# main.net
KiCad netlist of a schematic drawn in EAGLE
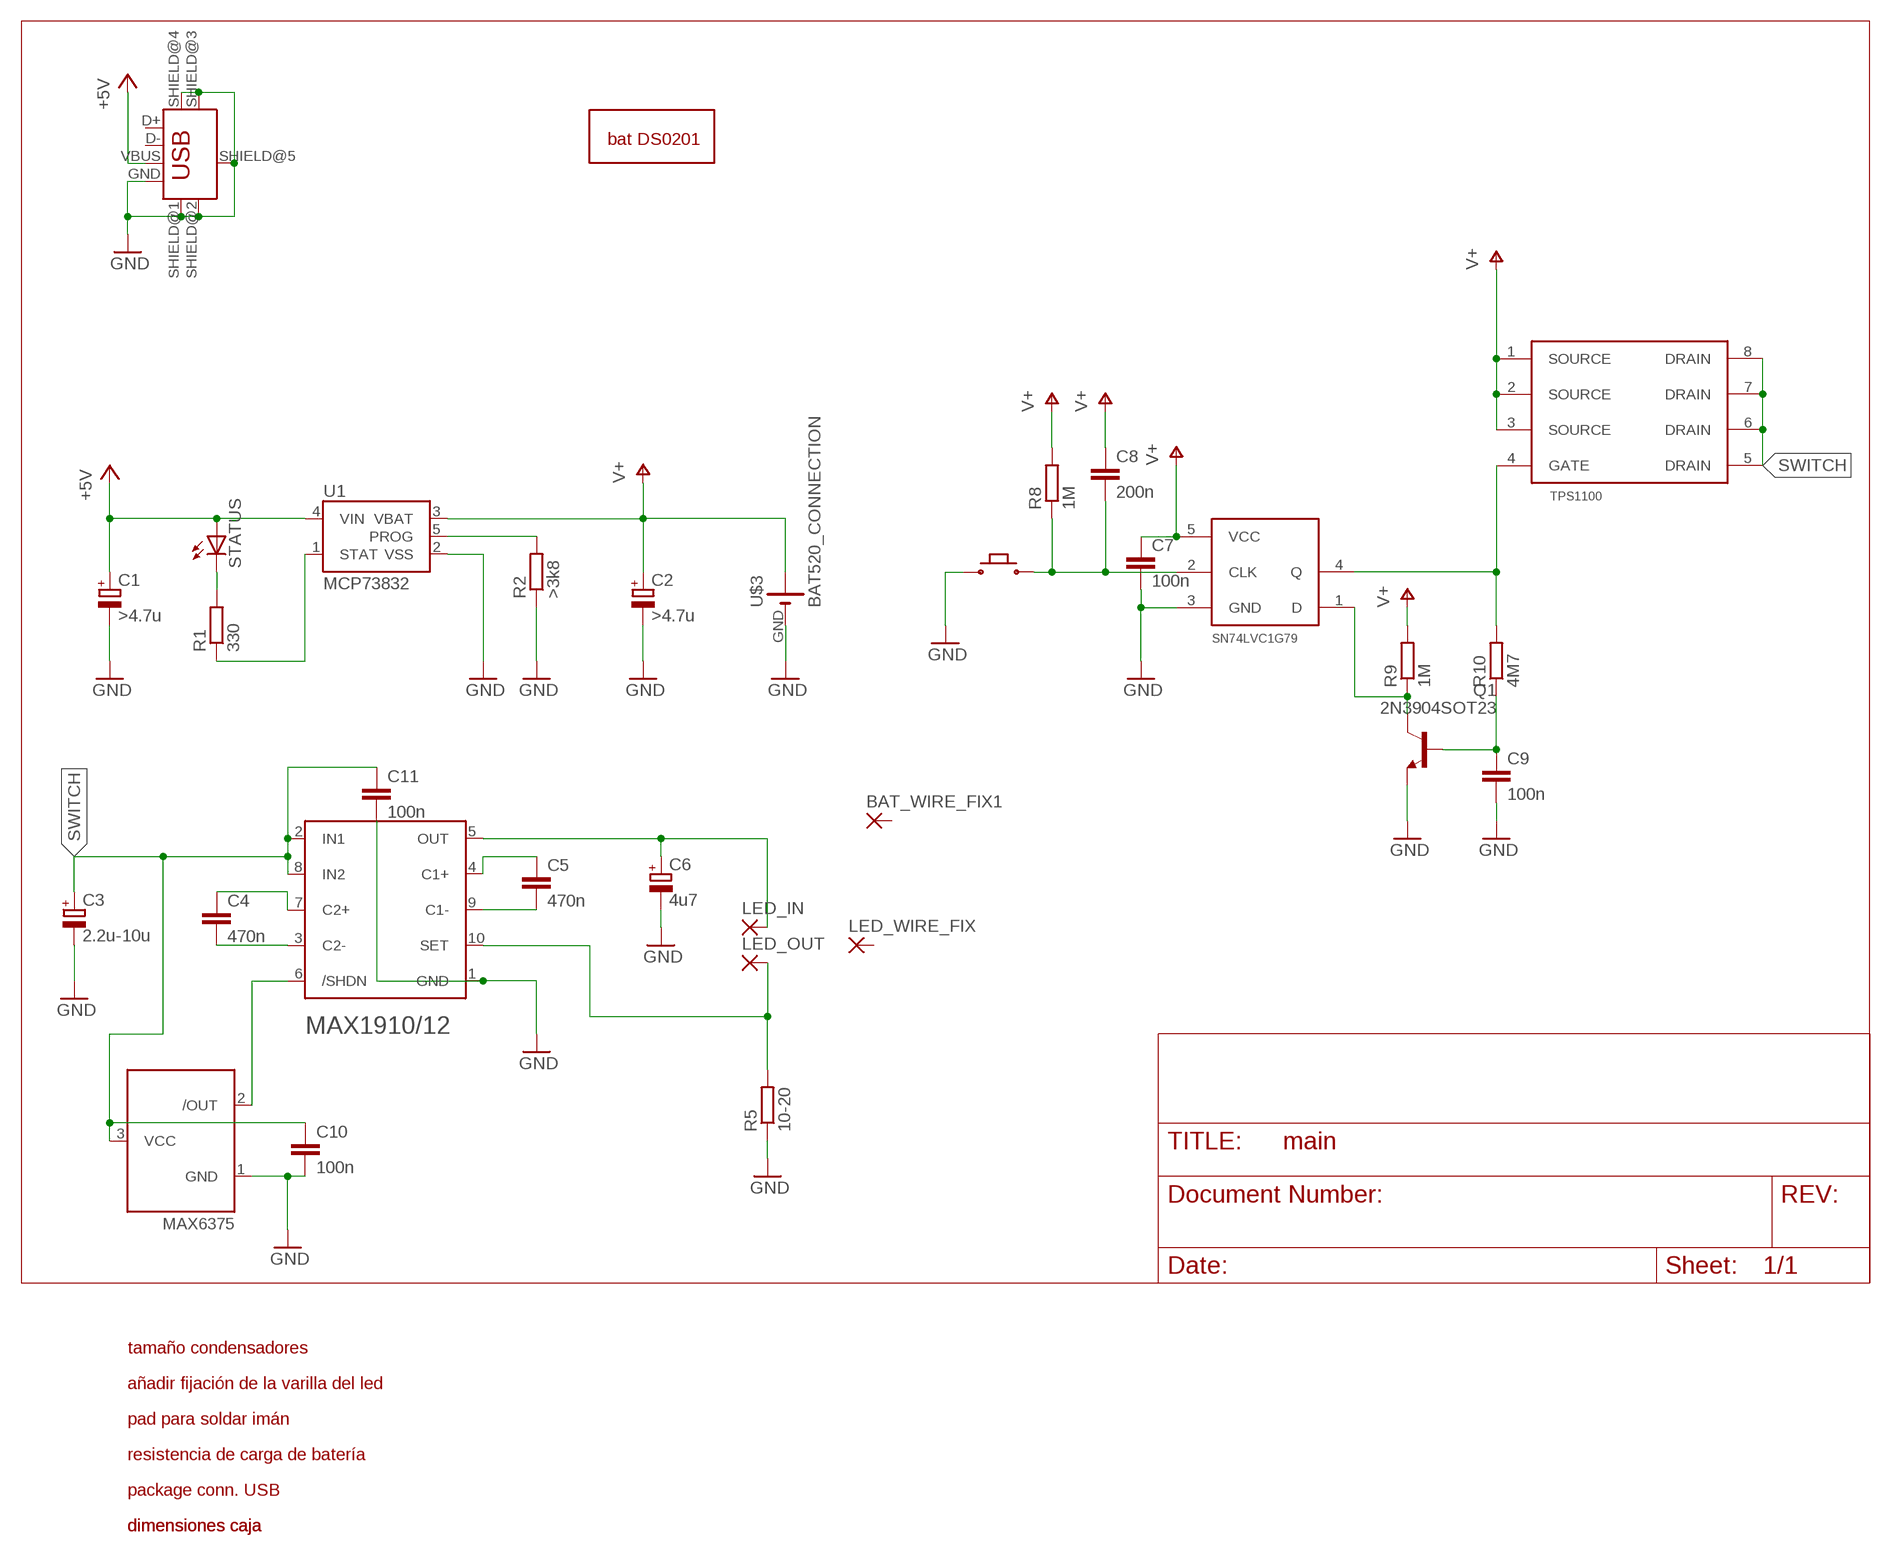
[diagram p0: schematic, sheet 1]

(export (version "E")
  (design (tool "Eeschema 10.0.6"))
  (components
    (comp (ref "BAT_WIRE_FIX1")
      (value "SMD5")
      (footprint "eagle-import:SMD2,54-5,08")
      (libsource (lib "eagle-import") (part "SMD5"))
    )
    (comp (ref "C1")
      (value ">4.7u")
      (footprint "eagle-import:SMC_B")
      (libsource (lib "eagle-import") (part "CPOL-EUSMCB"))
    )
    (comp (ref "C2")
      (value ">4.7u")
      (footprint "eagle-import:SMC_B")
      (libsource (lib "eagle-import") (part "CPOL-EUSMCB"))
    )
    (comp (ref "C3")
      (value "2.2u-10u")
      (footprint "eagle-import:SMC_B")
      (libsource (lib "eagle-import") (part "CPOL-EUSMCB"))
    )
    (comp (ref "C4")
      (value "470n")
      (footprint "eagle-import:C1206")
      (libsource (lib "eagle-import") (part "C-EUC1206"))
    )
    (comp (ref "C5")
      (value "470n")
      (footprint "eagle-import:C1206")
      (libsource (lib "eagle-import") (part "C-EUC1206"))
    )
    (comp (ref "C6")
      (value "4u7")
      (footprint "eagle-import:SMC_B")
      (libsource (lib "eagle-import") (part "CPOL-EUSMCB"))
    )
    (comp (ref "C7")
      (value "100n")
      (footprint "eagle-import:C1206")
      (libsource (lib "eagle-import") (part "C-EUC1206"))
    )
    (comp (ref "C8")
      (value "200n")
      (footprint "eagle-import:C1206")
      (libsource (lib "eagle-import") (part "C-EUC1206"))
    )
    (comp (ref "C9")
      (value "100n")
      (footprint "eagle-import:C1206")
      (libsource (lib "eagle-import") (part "C-EUC1206"))
    )
    (comp (ref "C10")
      (value "100n")
      (footprint "eagle-import:C1206")
      (libsource (lib "eagle-import") (part "C-EUC1206"))
    )
    (comp (ref "C11")
      (value "100n")
      (footprint "eagle-import:C1206")
      (libsource (lib "eagle-import") (part "C-EUC1206"))
    )
    (comp (ref "LED_IN")
      (value "SMD2")
      (footprint "eagle-import:SMD1,27-2,54")
      (libsource (lib "eagle-import") (part "SMD2"))
    )
    (comp (ref "LED_OUT")
      (value "SMD2")
      (footprint "eagle-import:SMD1,27-2,54")
      (libsource (lib "eagle-import") (part "SMD2"))
    )
    (comp (ref "LED_WIRE_FIX")
      (value "SMD5")
      (footprint "eagle-import:SMD2,54-5,08")
      (libsource (lib "eagle-import") (part "SMD5"))
    )
    (comp (ref "Q1")
      (value "2N3904SOT23")
      (footprint "eagle-import:SOT23")
      (libsource (lib "eagle-import") (part "2N3904SOT23"))
    )
    (comp (ref "R1")
      (value "330")
      (footprint "eagle-import:R1206")
      (libsource (lib "eagle-import") (part "R-EU_R1206"))
    )
    (comp (ref "R2")
      (value ">3k8")
      (footprint "eagle-import:R1206")
      (libsource (lib "eagle-import") (part "R-EU_R1206"))
    )
    (comp (ref "R5")
      (value "10-20")
      (footprint "eagle-import:R1206")
      (libsource (lib "eagle-import") (part "R-EU_R1206"))
    )
    (comp (ref "R8")
      (value "1M")
      (footprint "eagle-import:R0805")
      (libsource (lib "eagle-import") (part "R-EU_R0805"))
    )
    (comp (ref "R9")
      (value "1M")
      (footprint "eagle-import:R0805")
      (libsource (lib "eagle-import") (part "R-EU_R0805"))
    )
    (comp (ref "R10")
      (value "4M7")
      (footprint "eagle-import:R1206")
      (libsource (lib "eagle-import") (part "R-EU_R1206"))
    )
    (comp (ref "STATUS")
      (value "LEDCHIPLED_1206")
      (footprint "eagle-import:CHIPLED_1206")
      (libsource (lib "eagle-import") (part "LEDCHIPLED_1206"))
    )
    (comp (ref "U$1")
      (value "MAX1910/12")
      (footprint "eagle-import:UMAX_USOP_10L")
      (libsource (lib "eagle-import") (part "MAX1910/12"))
    )
    (comp (ref "U$2")
      (value "MAX6375")
      (footprint "eagle-import:SC70-3-W")
      (libsource (lib "eagle-import") (part "MAX6375"))
    )
    (comp (ref "U$3")
      (value "BAT520_CONNECTION")
      (footprint "eagle-import:BAT520_CONN_SMD")
      (libsource (lib "eagle-import") (part "BAT520_CONNECTION"))
    )
    (comp (ref "U$4")
      (value "BAT_DS0201_PACKAGE")
      (footprint "eagle-import:BAT_DS0201")
      (libsource (lib "eagle-import") (part "BAT_DS0201_PACKAGE"))
    )
    (comp (ref "U$5")
      (value "MICROUSB_B")
      (footprint "eagle-import:USB-MICROB")
      (libsource (lib "eagle-import") (part "MICROUSB_B"))
    )
    (comp (ref "U$6")
      (value "MICROBUTTONE-MERCHAN")
      (footprint "eagle-import:MICROBUTTON_2")
      (libsource (lib "eagle-import") (part "MICROBUTTONE-MERCHAN"))
    )
    (comp (ref "U$7")
      (value "SN74LVC1G79")
      (footprint "eagle-import:SOT23-5")
      (libsource (lib "eagle-import") (part "SN74LVC1G79"))
    )
    (comp (ref "U$8")
      (value "TPS1100")
      (footprint "eagle-import:SO08")
      (libsource (lib "eagle-import") (part "TPS1100"))
    )
    (comp (ref "U1")
      (value "MCP73832")
      (footprint "eagle-import:SOT23-5")
      (libsource (lib "eagle-import") (part "MCP73832"))
    )
  )
  (nets
    (net (code "1") (name "+5V") (class "Default")
      (node (ref "C1") (pin "+") (pinfunction "+_+") (pintype "passive"))
      (node (ref "STATUS") (pin "A") (pinfunction "A_A") (pintype "passive"))
      (node (ref "U$5") (pin "VBUS") (pinfunction "VBUS_VBUS") (pintype "bidirectional"))
      (node (ref "U1") (pin "4") (pinfunction "VIN_4") (pintype "power_in"))
    )
    (net (code "2") (name "GND") (class "Default")
      (node (ref "C1") (pin "-") (pinfunction "-_-") (pintype "passive"))
      (node (ref "C10") (pin "2") (pinfunction "2_2") (pintype "passive"))
      (node (ref "C11") (pin "2") (pinfunction "2_2") (pintype "passive"))
      (node (ref "C2") (pin "-") (pinfunction "-_-") (pintype "passive"))
      (node (ref "C3") (pin "-") (pinfunction "-_-") (pintype "passive"))
      (node (ref "C6") (pin "-") (pinfunction "-_-") (pintype "passive"))
      (node (ref "C7") (pin "2") (pinfunction "2_2") (pintype "passive"))
      (node (ref "C9") (pin "2") (pinfunction "2_2") (pintype "passive"))
      (node (ref "Q1") (pin "2") (pinfunction "E_2") (pintype "passive"))
      (node (ref "R2") (pin "1") (pinfunction "1_1") (pintype "passive"))
      (node (ref "R5") (pin "1") (pinfunction "1_1") (pintype "passive"))
      (node (ref "U$1") (pin "1") (pinfunction "GND_1") (pintype "power_in"))
      (node (ref "U$2") (pin "1") (pinfunction "GND_1") (pintype "power_in"))
      (node (ref "U$3") (pin "GND") (pinfunction "-_GND") (pintype "passive"))
      (node (ref "U$5") (pin "GND") (pinfunction "GND_GND") (pintype "bidirectional"))
      (node (ref "U$5") (pin "SHIELD@1") (pinfunction "SHIELD_SHIELD@1") (pintype "bidirectional"))
      (node (ref "U$5") (pin "SHIELD@2") (pinfunction "SHIELD_SHIELD@2") (pintype "bidirectional"))
      (node (ref "U$5") (pin "SHIELD@3") (pinfunction "SHIELD_SHIELD@3") (pintype "bidirectional"))
      (node (ref "U$5") (pin "SHIELD@4") (pinfunction "SHIELD_SHIELD@4") (pintype "bidirectional"))
      (node (ref "U$5") (pin "SHIELD@5") (pinfunction "SHIELD_SHIELD@5") (pintype "bidirectional"))
      (node (ref "U$6") (pin "P$1") (pinfunction "P$1_P$1") (pintype "bidirectional"))
      (node (ref "U$7") (pin "3") (pinfunction "GND_3") (pintype "bidirectional"))
      (node (ref "U1") (pin "2") (pinfunction "VSS_2") (pintype "power_in"))
    )
    (net (code "3") (name "Net-(LED_IN-P)") (class "Default")
      (node (ref "C6") (pin "+") (pinfunction "+_+") (pintype "passive"))
      (node (ref "LED_IN") (pin "1") (pinfunction "P_1") (pintype "passive"))
      (node (ref "U$1") (pin "5") (pinfunction "OUT_5") (pintype "output"))
    )
    (net (code "4") (name "Net-(LED_OUT-P)") (class "Default")
      (node (ref "LED_OUT") (pin "1") (pinfunction "P_1") (pintype "passive"))
      (node (ref "R5") (pin "2") (pinfunction "2_2") (pintype "passive"))
      (node (ref "U$1") (pin "10") (pinfunction "SET_10") (pintype "input"))
    )
    (net (code "5") (name "Net-(Q1-B)") (class "Default")
      (node (ref "C9") (pin "1") (pinfunction "1_1") (pintype "passive"))
      (node (ref "Q1") (pin "1") (pinfunction "B_1") (pintype "passive"))
      (node (ref "R10") (pin "1") (pinfunction "1_1") (pintype "passive"))
    )
    (net (code "6") (name "Net-(Q1-C)") (class "Default")
      (node (ref "Q1") (pin "3") (pinfunction "C_3") (pintype "passive"))
      (node (ref "R9") (pin "1") (pinfunction "1_1") (pintype "passive"))
      (node (ref "U$7") (pin "1") (pinfunction "D_1") (pintype "bidirectional"))
    )
    (net (code "7") (name "Net-(R1-Pad2)") (class "Default")
      (node (ref "R1") (pin "2") (pinfunction "2_2") (pintype "passive"))
      (node (ref "STATUS") (pin "C") (pinfunction "C_C") (pintype "passive"))
    )
    (net (code "8") (name "Net-(U$1-C1+)") (class "Default")
      (node (ref "C5") (pin "1") (pinfunction "1_1") (pintype "passive"))
      (node (ref "U$1") (pin "4") (pinfunction "C1+_4") (pintype "bidirectional"))
    )
    (net (code "9") (name "Net-(U$1-C1-)") (class "Default")
      (node (ref "C5") (pin "2") (pinfunction "2_2") (pintype "passive"))
      (node (ref "U$1") (pin "9") (pinfunction "C1-_9") (pintype "bidirectional"))
    )
    (net (code "10") (name "Net-(U$1-C2+)") (class "Default")
      (node (ref "C4") (pin "1") (pinfunction "1_1") (pintype "passive"))
      (node (ref "U$1") (pin "7") (pinfunction "C2+_7") (pintype "bidirectional"))
    )
    (net (code "11") (name "Net-(U$1-C2-)") (class "Default")
      (node (ref "C4") (pin "2") (pinfunction "2_2") (pintype "passive"))
      (node (ref "U$1") (pin "3") (pinfunction "C2-_3") (pintype "bidirectional"))
    )
    (net (code "12") (name "Net-(U$1-{slash}SHDN)") (class "Default")
      (node (ref "U$1") (pin "6") (pinfunction "/SHDN_6") (pintype "bidirectional"))
      (node (ref "U$2") (pin "2") (pinfunction "/OUT_2") (pintype "output"))
    )
    (net (code "13") (name "Net-(U$7-CLK)") (class "Default")
      (node (ref "C8") (pin "2") (pinfunction "2_2") (pintype "passive"))
      (node (ref "R8") (pin "1") (pinfunction "1_1") (pintype "passive"))
      (node (ref "U$6") (pin "P$2") (pinfunction "P$2_P$2") (pintype "bidirectional"))
      (node (ref "U$7") (pin "2") (pinfunction "CLK_2") (pintype "bidirectional"))
    )
    (net (code "14") (name "Net-(U$7-Q)") (class "Default")
      (node (ref "R10") (pin "2") (pinfunction "2_2") (pintype "passive"))
      (node (ref "U$7") (pin "4") (pinfunction "Q_4") (pintype "bidirectional"))
      (node (ref "U$8") (pin "4") (pinfunction "GATE_4") (pintype "bidirectional"))
    )
    (net (code "15") (name "Net-(U1-PROG)") (class "Default")
      (node (ref "R2") (pin "2") (pinfunction "2_2") (pintype "passive"))
      (node (ref "U1") (pin "5") (pinfunction "PROG_5") (pintype "input"))
    )
    (net (code "16") (name "Net-(U1-STAT)") (class "Default")
      (node (ref "R1") (pin "1") (pinfunction "1_1") (pintype "passive"))
      (node (ref "U1") (pin "1") (pinfunction "STAT_1") (pintype "output"))
    )
    (net (code "17") (name "SWITCH") (class "Default")
      (node (ref "C10") (pin "1") (pinfunction "1_1") (pintype "passive"))
      (node (ref "C11") (pin "1") (pinfunction "1_1") (pintype "passive"))
      (node (ref "C3") (pin "+") (pinfunction "+_+") (pintype "passive"))
      (node (ref "U$1") (pin "2") (pinfunction "IN1_2") (pintype "power_in"))
      (node (ref "U$1") (pin "8") (pinfunction "IN2_8") (pintype "power_in"))
      (node (ref "U$2") (pin "3") (pinfunction "VCC_3") (pintype "power_in"))
      (node (ref "U$8") (pin "5") (pinfunction "DRAIN_5") (pintype "bidirectional"))
      (node (ref "U$8") (pin "6") (pinfunction "DRAIN_6") (pintype "bidirectional"))
      (node (ref "U$8") (pin "7") (pinfunction "DRAIN_7") (pintype "bidirectional"))
      (node (ref "U$8") (pin "8") (pinfunction "DRAIN_8") (pintype "bidirectional"))
    )
    (net (code "18") (name "V+") (class "Default")
      (node (ref "C2") (pin "+") (pinfunction "+_+") (pintype "passive"))
      (node (ref "C7") (pin "1") (pinfunction "1_1") (pintype "passive"))
      (node (ref "C8") (pin "1") (pinfunction "1_1") (pintype "passive"))
      (node (ref "R8") (pin "2") (pinfunction "2_2") (pintype "passive"))
      (node (ref "R9") (pin "2") (pinfunction "2_2") (pintype "passive"))
      (node (ref "U$3") (pin "VCC") (pinfunction "+_VCC") (pintype "passive"))
      (node (ref "U$7") (pin "5") (pinfunction "VCC_5") (pintype "bidirectional"))
      (node (ref "U$8") (pin "1") (pinfunction "SOURCE_1") (pintype "bidirectional"))
      (node (ref "U$8") (pin "2") (pinfunction "SOURCE_2") (pintype "bidirectional"))
      (node (ref "U$8") (pin "3") (pinfunction "SOURCE_3") (pintype "bidirectional"))
      (node (ref "U1") (pin "3") (pinfunction "VBAT_3") (pintype "power_in"))
    )
    (net (code "19") (name "unconnected-(BAT_WIRE_FIX1-P-Pad1)") (class "Default")
      (node (ref "BAT_WIRE_FIX1") (pin "1") (pinfunction "P_1") (pintype "passive"))
    )
    (net (code "20") (name "unconnected-(LED_WIRE_FIX-P-Pad1)") (class "Default")
      (node (ref "LED_WIRE_FIX") (pin "1") (pinfunction "P_1") (pintype "passive"))
    )
    (net (code "21") (name "unconnected-(U$5-PadD+)") (class "Default")
      (node (ref "U$5") (pin "D+") (pinfunction "D+_D+") (pintype "bidirectional"))
    )
    (net (code "22") (name "unconnected-(U$5-PadD-)") (class "Default")
      (node (ref "U$5") (pin "D-") (pinfunction "D-_D-") (pintype "bidirectional"))
    )
  )
)
